# MicroTeleinfo.net
KiCad netlist of a schematic drawn in EAGLE
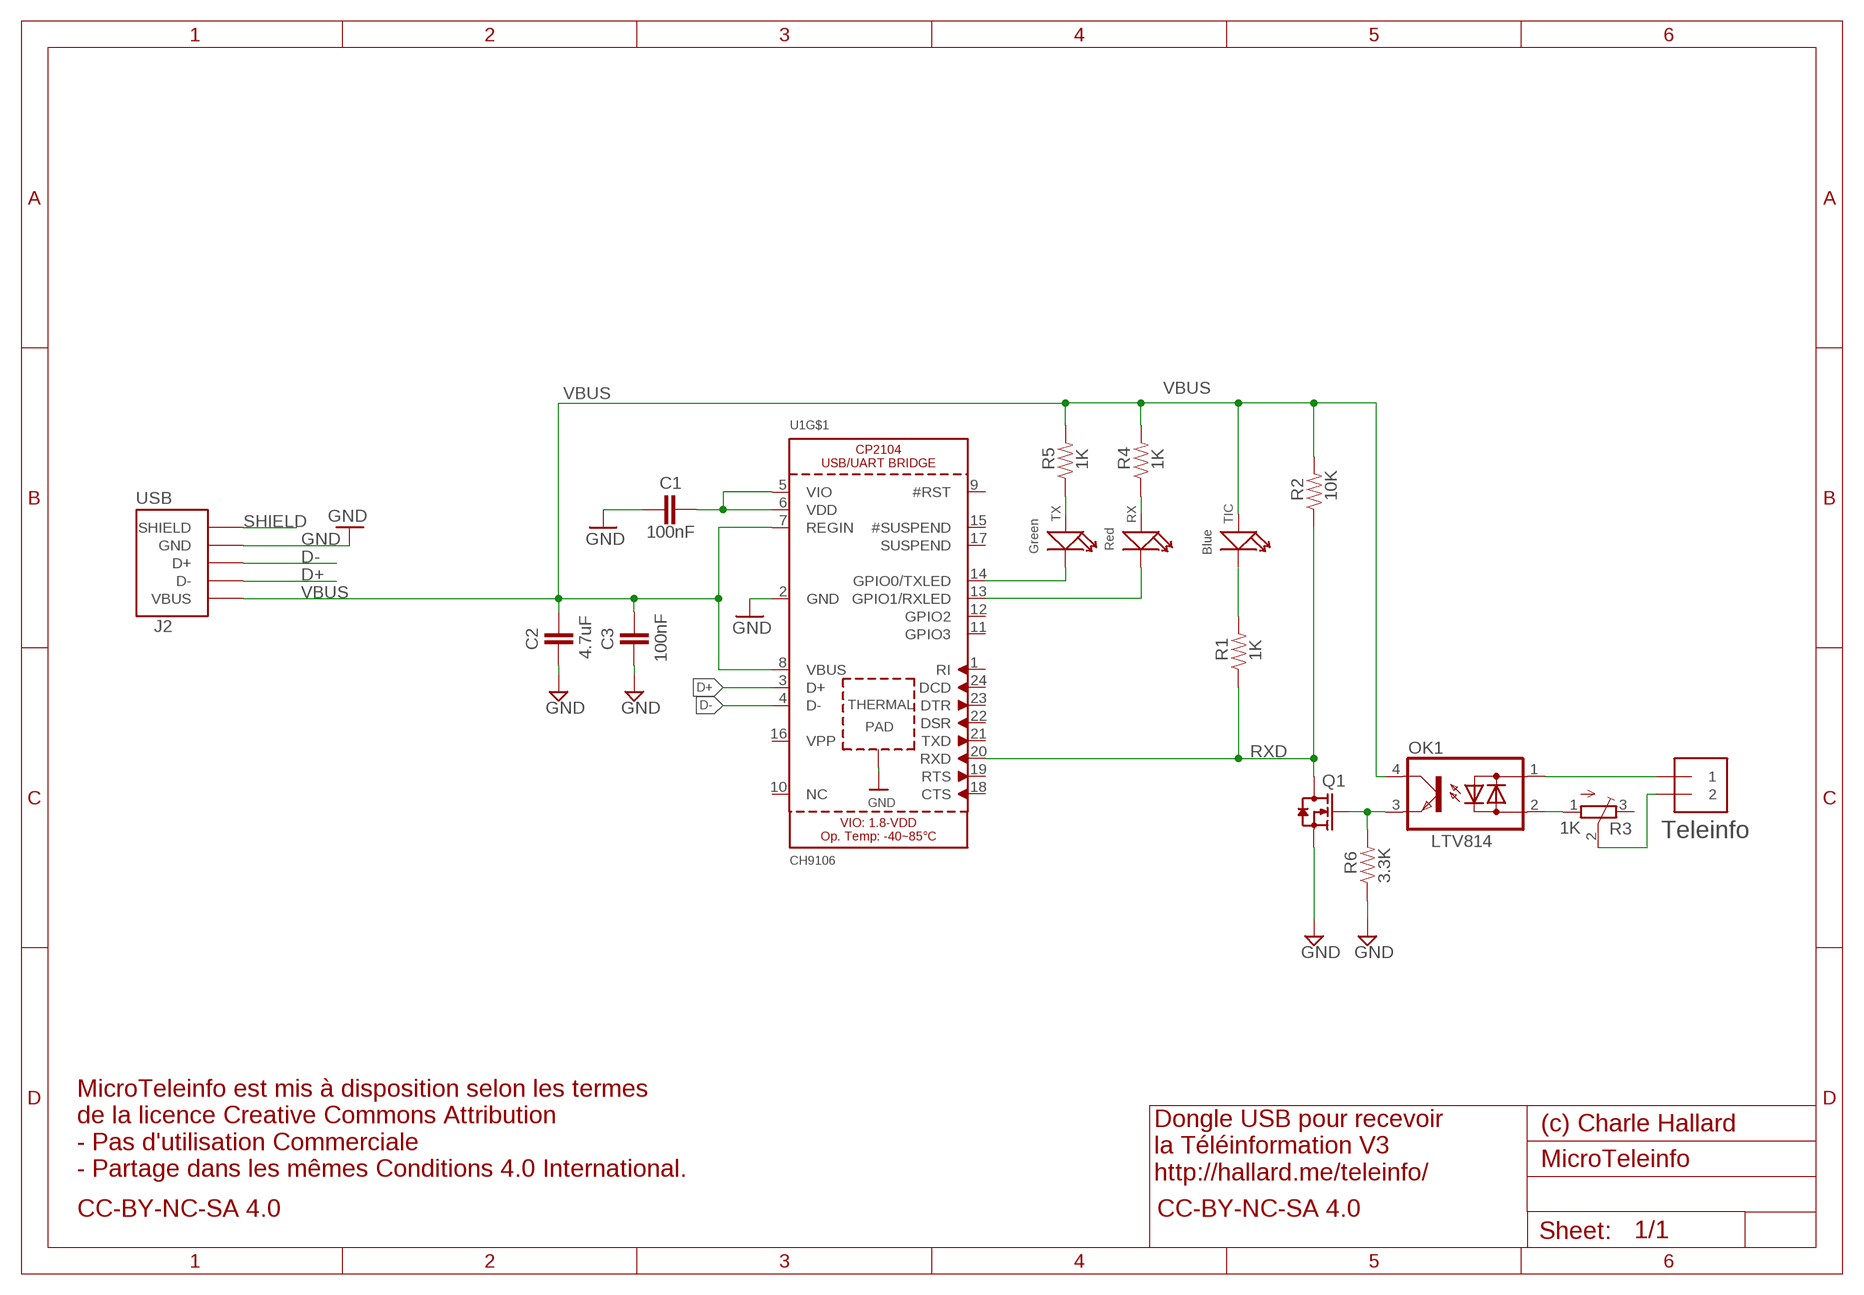
[diagram p0: schematic, sheet 1]

(export (version "E")
  (design (tool "Eeschema 10.0.6"))
  (components
    (comp (ref "C1")
      (value "100nF")
      (footprint "eagle-import:0402-CAP-OK")
      (libsource (lib "eagle-import") (part "CAP0402-CAP-OK"))
    )
    (comp (ref "C2")
      (value "4.7uF")
      (footprint "eagle-import:0402-CAP-OK")
      (libsource (lib "eagle-import") (part "CAP0402-CAP-OK"))
    )
    (comp (ref "C3")
      (value "100nF")
      (footprint "eagle-import:0402-CAP-OK")
      (libsource (lib "eagle-import") (part "CAP0402-CAP-OK"))
    )
    (comp (ref "J1")
      (value "1X2-3.5MM")
      (footprint "eagle-import:1X2-3.5MM")
      (libsource (lib "eagle-import") (part "1X2-3.5MM"))
    )
    (comp (ref "J2")
      (value "USB")
      (footprint "eagle-import:GCT_USB1061-XX-X-X_REVA")
      (fields (field (name "MF") "Global Connector Technology") (field (name "MP") "USB1061-GF-L-A"))
      (libsource (lib "eagle-import") (part "USB1061-XX-X-X_REVA"))
    )
    (comp (ref "OK1")
      (value "LTV814")
      (footprint "eagle-import:DIL4-SMD")
      (fields (field (name "MF") "VISHAY/TELEFUNKEN") (field (name "MPN") "SFH6206-3"))
      (libsource (lib "eagle-import") (part "SFH6206"))
    )
    (comp (ref "Q1")
      (value "CJ2302")
      (footprint "eagle-import:SOT-323-3")
      (libsource (lib "eagle-import") (part "SMD-MOSFET-N-CH-20V-2.1A-CJ2302(SOT-23)"))
    )
    (comp (ref "R1")
      (value "1K")
      (footprint "eagle-import:0402-RES")
      (libsource (lib "eagle-import") (part "RESISTOR0402-RES"))
    )
    (comp (ref "R2")
      (value "10K")
      (footprint "eagle-import:0402-RES")
      (libsource (lib "eagle-import") (part "RESISTOR0402-RES"))
    )
    (comp (ref "R3")
      (value "1K")
      (footprint "eagle-import:TC33X")
      (libsource (lib "eagle-import") (part "TRIMPOTTC33X"))
    )
    (comp (ref "R4")
      (value "1K")
      (footprint "eagle-import:0402-RES")
      (libsource (lib "eagle-import") (part "RESISTOR0402-RES"))
    )
    (comp (ref "R5")
      (value "1K")
      (footprint "eagle-import:0402-RES")
      (libsource (lib "eagle-import") (part "RESISTOR0402-RES"))
    )
    (comp (ref "R6")
      (value "3.3K")
      (footprint "eagle-import:0402-RES")
      (libsource (lib "eagle-import") (part "RESISTOR0402-RES"))
    )
    (comp (ref "RX")
      (value "Red")
      (footprint "eagle-import:LED-0402")
      (fields (field (name "MPN") "BL-HB337A-AV-TRB"))
      (libsource (lib "eagle-import") (part "SMD-LED-CLEAR-BLUE(0402)"))
    )
    (comp (ref "TIC")
      (value "Blue")
      (footprint "eagle-import:LED-0402")
      (fields (field (name "MPN") "BL-HB337A-AV-TRB"))
      (libsource (lib "eagle-import") (part "SMD-LED-CLEAR-BLUE(0402)"))
    )
    (comp (ref "TX")
      (value "Green")
      (footprint "eagle-import:LED-0402")
      (fields (field (name "MPN") "BL-HB337A-AV-TRB"))
      (libsource (lib "eagle-import") (part "SMD-LED-CLEAR-BLUE(0402)"))
    )
    (comp (ref "U1")
      (value "CH9106")
      (footprint "eagle-import:QFN24_4MM_SMSC")
      (libsource (lib "eagle-import") (part "CP2104"))
    )
  )
  (nets
    (net (code "1") (name "/RXD") (class "Default")
      (node (ref "Q1") (pin "3") (pinfunction "D_3") (pintype "passive"))
      (node (ref "R1") (pin "1") (pinfunction "1_1") (pintype "passive"))
      (node (ref "R2") (pin "1") (pinfunction "1_1") (pintype "passive"))
      (node (ref "U1") (pin "20") (pinfunction "RXD_20") (pintype "input"))
    )
    (net (code "2") (name "/SHIELD") (class "Default")
      (node (ref "J2") (pin "5") (pinfunction "SHIELD_5") (pintype "power_in"))
      (node (ref "J2") (pin "6") (pinfunction "SHIELD_6") (pintype "power_in"))
    )
    (net (code "3") (name "/VBUS") (class "Default")
      (node (ref "C2") (pin "1") (pinfunction "1_1") (pintype "passive"))
      (node (ref "C3") (pin "2") (pinfunction "2_2") (pintype "passive"))
      (node (ref "J2") (pin "1") (pinfunction "VBUS_1") (pintype "power_in"))
      (node (ref "OK1") (pin "4") (pinfunction "C_4") (pintype "passive"))
      (node (ref "R2") (pin "2") (pinfunction "2_2") (pintype "passive"))
      (node (ref "R4") (pin "2") (pinfunction "2_2") (pintype "passive"))
      (node (ref "R5") (pin "2") (pinfunction "2_2") (pintype "passive"))
      (node (ref "TIC") (pin "+") (pinfunction "+_+") (pintype "passive"))
      (node (ref "U1") (pin "7") (pinfunction "REGIN_7") (pintype "power_in"))
      (node (ref "U1") (pin "8") (pinfunction "VBUS_8") (pintype "power_in"))
    )
    (net (code "4") (name "D+") (class "Default")
      (node (ref "J2") (pin "3") (pinfunction "D+_3") (pintype "bidirectional"))
      (node (ref "U1") (pin "3") (pinfunction "D+_3") (pintype "bidirectional"))
    )
    (net (code "5") (name "D-") (class "Default")
      (node (ref "J2") (pin "2") (pinfunction "D-_2") (pintype "bidirectional"))
      (node (ref "U1") (pin "4") (pinfunction "D-_4") (pintype "bidirectional"))
    )
    (net (code "6") (name "GND") (class "Default")
      (node (ref "C1") (pin "1") (pinfunction "1_1") (pintype "passive"))
      (node (ref "C2") (pin "2") (pinfunction "2_2") (pintype "passive"))
      (node (ref "C3") (pin "1") (pinfunction "1_1") (pintype "passive"))
      (node (ref "J2") (pin "4") (pinfunction "GND_4") (pintype "power_in"))
      (node (ref "Q1") (pin "2") (pinfunction "S_2") (pintype "passive"))
      (node (ref "R6") (pin "1") (pinfunction "1_1") (pintype "passive"))
      (node (ref "U1") (pin "2") (pinfunction "GND_2") (pintype "power_in"))
      (node (ref "U1") (pin "THERM") (pinfunction "TP_THERM") (pintype "power_in"))
    )
    (net (code "7") (name "Net-(OK1-AC1)") (class "Default")
      (node (ref "J1") (pin "1") (pinfunction "1_1") (pintype "passive"))
      (node (ref "OK1") (pin "1") (pinfunction "AC1_1") (pintype "passive"))
    )
    (net (code "8") (name "Net-(OK1-AC2)") (class "Default")
      (node (ref "OK1") (pin "2") (pinfunction "AC2_2") (pintype "passive"))
      (node (ref "R3") (pin "1") (pinfunction "A_1") (pintype "passive"))
    )
    (net (code "9") (name "Net-(OK1-E)") (class "Default")
      (node (ref "OK1") (pin "3") (pinfunction "E_3") (pintype "passive"))
      (node (ref "Q1") (pin "1") (pinfunction "G_1") (pintype "passive"))
      (node (ref "R6") (pin "2") (pinfunction "2_2") (pintype "passive"))
    )
    (net (code "10") (name "Net-(R1-Pad2)") (class "Default")
      (node (ref "R1") (pin "2") (pinfunction "2_2") (pintype "passive"))
      (node (ref "TIC") (pin "-") (pinfunction "-_-") (pintype "passive"))
    )
    (net (code "11") (name "Net-(R3-S)") (class "Default")
      (node (ref "J1") (pin "2") (pinfunction "2_2") (pintype "passive"))
      (node (ref "R3") (pin "2") (pinfunction "S_2") (pintype "passive"))
    )
    (net (code "12") (name "Net-(R4-Pad1)") (class "Default")
      (node (ref "R4") (pin "1") (pinfunction "1_1") (pintype "passive"))
      (node (ref "RX") (pin "+") (pinfunction "+_+") (pintype "passive"))
    )
    (net (code "13") (name "Net-(R5-Pad1)") (class "Default")
      (node (ref "R5") (pin "1") (pinfunction "1_1") (pintype "passive"))
      (node (ref "TX") (pin "+") (pinfunction "+_+") (pintype "passive"))
    )
    (net (code "14") (name "Net-(U1A-GPIO0{slash}TXLED)") (class "Default")
      (node (ref "TX") (pin "-") (pinfunction "-_-") (pintype "passive"))
      (node (ref "U1") (pin "14") (pinfunction "GPIO0/TXLED_14") (pintype "bidirectional"))
    )
    (net (code "15") (name "Net-(U1A-GPIO1{slash}RXLED)") (class "Default")
      (node (ref "RX") (pin "-") (pinfunction "-_-") (pintype "passive"))
      (node (ref "U1") (pin "13") (pinfunction "GPIO1/RXLED_13") (pintype "bidirectional"))
    )
    (net (code "16") (name "Net-(U1A-VDD)") (class "Default")
      (node (ref "C1") (pin "2") (pinfunction "2_2") (pintype "passive"))
      (node (ref "U1") (pin "5") (pinfunction "VIO_5") (pintype "power_in"))
      (node (ref "U1") (pin "6") (pinfunction "VDD_6") (pintype "power_in"))
    )
    (net (code "17") (name "unconnected-(R3-E-Pad3)") (class "Default")
      (node (ref "R3") (pin "3") (pinfunction "E_3") (pintype "passive"))
    )
    (net (code "18") (name "unconnected-(U1A-#RST-Pad9)") (class "Default")
      (node (ref "U1") (pin "9") (pinfunction "#RST_9") (pintype "bidirectional"))
    )
    (net (code "19") (name "unconnected-(U1A-#SUSPEND-Pad15)") (class "Default")
      (node (ref "U1") (pin "15") (pinfunction "#SUSPEND_15") (pintype "output"))
    )
    (net (code "20") (name "unconnected-(U1A-CTS-Pad18)") (class "Default")
      (node (ref "U1") (pin "18") (pinfunction "CTS_18") (pintype "input"))
    )
    (net (code "21") (name "unconnected-(U1A-DCD-Pad24)") (class "Default")
      (node (ref "U1") (pin "24") (pinfunction "DCD_24") (pintype "input"))
    )
    (net (code "22") (name "unconnected-(U1A-DSR-Pad22)") (class "Default")
      (node (ref "U1") (pin "22") (pinfunction "DSR_22") (pintype "input"))
    )
    (net (code "23") (name "unconnected-(U1A-DTR-Pad23)") (class "Default")
      (node (ref "U1") (pin "23") (pinfunction "DTR_23") (pintype "output"))
    )
    (net (code "24") (name "unconnected-(U1A-GPIO2-Pad12)") (class "Default")
      (node (ref "U1") (pin "12") (pinfunction "GPIO2_12") (pintype "bidirectional"))
    )
    (net (code "25") (name "unconnected-(U1A-GPIO3-Pad11)") (class "Default")
      (node (ref "U1") (pin "11") (pinfunction "GPIO3_11") (pintype "bidirectional"))
    )
    (net (code "26") (name "unconnected-(U1A-NC-Pad10)") (class "Default")
      (node (ref "U1") (pin "10") (pinfunction "NC_10") (pintype "no_connect"))
    )
    (net (code "27") (name "unconnected-(U1A-RI-Pad1)") (class "Default")
      (node (ref "U1") (pin "1") (pinfunction "RI_1") (pintype "input"))
    )
    (net (code "28") (name "unconnected-(U1A-RTS-Pad19)") (class "Default")
      (node (ref "U1") (pin "19") (pinfunction "RTS_19") (pintype "output"))
    )
    (net (code "29") (name "unconnected-(U1A-SUSPEND-Pad17)") (class "Default")
      (node (ref "U1") (pin "17") (pinfunction "SUSPEND_17") (pintype "output"))
    )
    (net (code "30") (name "unconnected-(U1A-TXD-Pad21)") (class "Default")
      (node (ref "U1") (pin "21") (pinfunction "TXD_21") (pintype "output"))
    )
    (net (code "31") (name "unconnected-(U1A-VPP-Pad16)") (class "Default")
      (node (ref "U1") (pin "16") (pinfunction "VPP_16") (pintype "bidirectional"))
    )
  )
)
